# STM32F103VBT6-design.net
KiCad netlist of a schematic drawn in Altium Designer
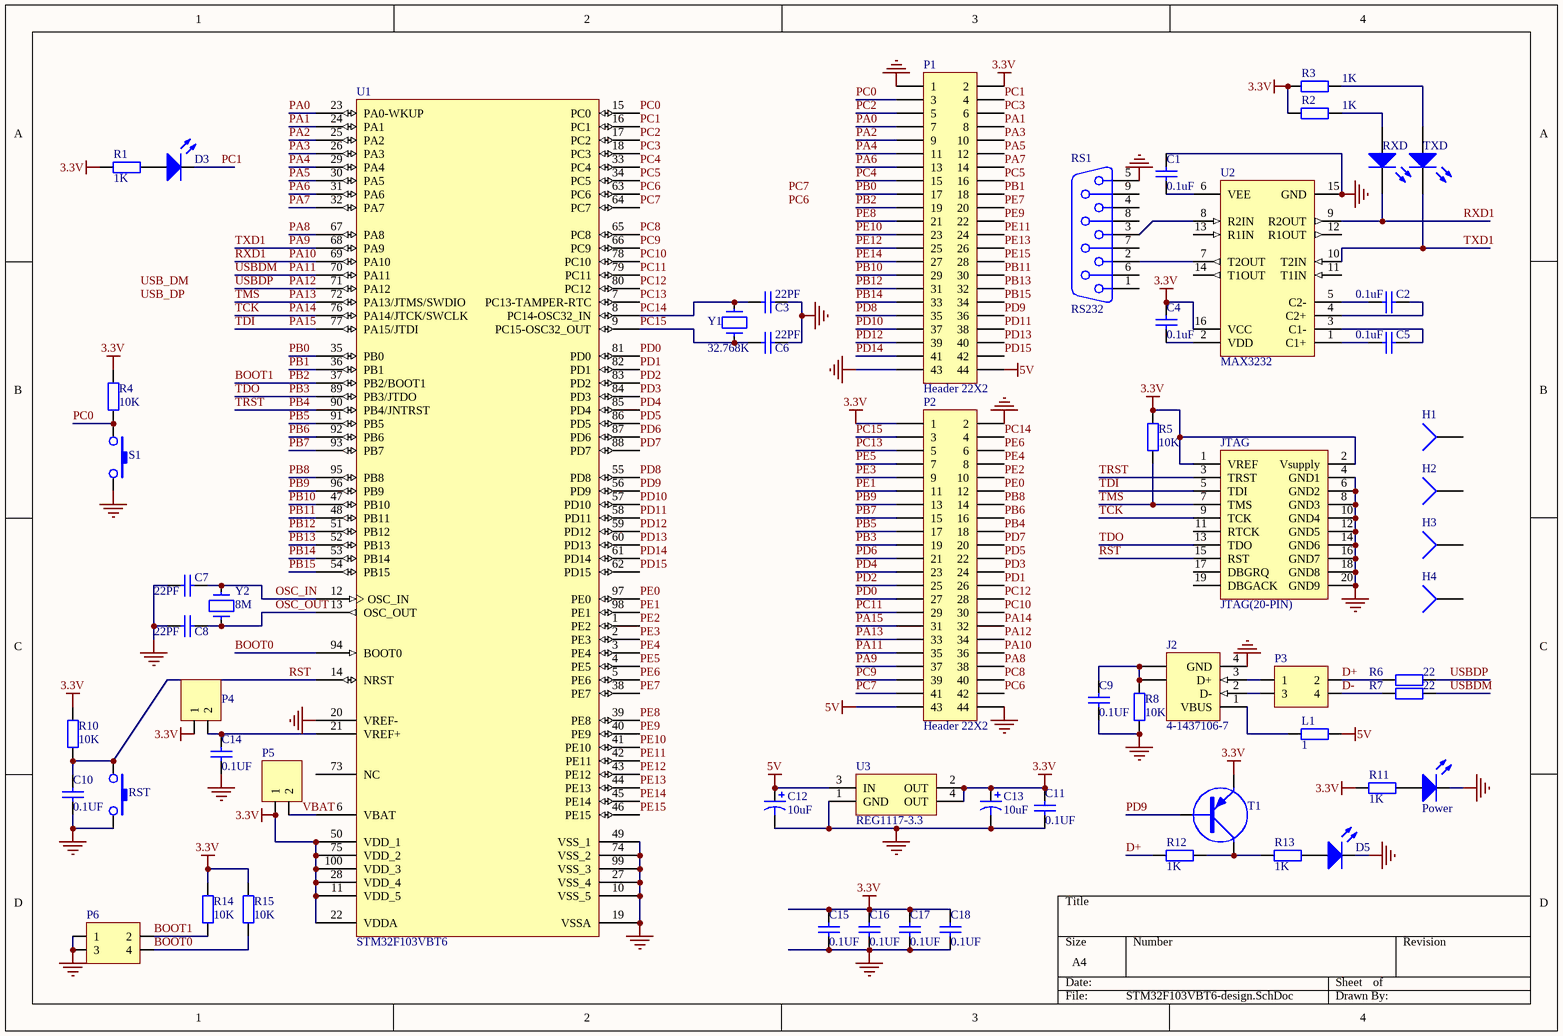
[diagram p0: STM32F103VBT6-design.SchDoc]

(export (version "E")
  (design (tool "Eeschema 10.0.6"))
  (components
    (comp (ref "C1")
      (value "0.1uF")
      (footprint "0805-S")
      (description "Capacitor")
      (fields (field (name "Comment") "Cap") (field (name "PUBLISHER") "Altium Limited"))
      (libsource (lib "Miscellaneous Devices") (part "Cap"))
    )
    (comp (ref "C2")
      (value "0.1uF")
      (footprint "0805-S")
      (description "Capacitor")
      (fields (field (name "Comment") "Cap") (field (name "PUBLISHER") "Altium Limited"))
      (libsource (lib "Miscellaneous Devices") (part "Cap"))
    )
    (comp (ref "C3")
      (value "22PF")
      (footprint "0805-S")
      (description "Capacitor")
      (fields (field (name "Comment") "Cap") (field (name "PUBLISHER") "Altium Limited"))
      (libsource (lib "Miscellaneous Devices") (part "Cap"))
    )
    (comp (ref "C4")
      (value "0.1uF")
      (footprint "0805-S")
      (description "Capacitor")
      (fields (field (name "Comment") "Cap") (field (name "PUBLISHER") "Altium Limited"))
      (libsource (lib "Miscellaneous Devices") (part "Cap"))
    )
    (comp (ref "C5")
      (value "0.1uF")
      (footprint "0805-S")
      (description "Capacitor")
      (fields (field (name "Comment") "Cap") (field (name "PUBLISHER") "Altium Limited"))
      (libsource (lib "Miscellaneous Devices") (part "Cap"))
    )
    (comp (ref "C6")
      (value "22PF")
      (footprint "0805-S")
      (description "Capacitor")
      (fields (field (name "Comment") "Cap") (field (name "PUBLISHER") "Altium Limited"))
      (libsource (lib "Miscellaneous Devices") (part "Cap"))
    )
    (comp (ref "C7")
      (value "22PF")
      (footprint "0805-S")
      (description "Capacitor")
      (fields (field (name "Comment") "Cap") (field (name "PUBLISHER") "Altium Limited"))
      (libsource (lib "Miscellaneous Devices") (part "Cap"))
    )
    (comp (ref "C8")
      (value "22PF")
      (footprint "0805-S")
      (description "Capacitor")
      (fields (field (name "Comment") "Cap") (field (name "PUBLISHER") "Altium Limited"))
      (libsource (lib "Miscellaneous Devices") (part "Cap"))
    )
    (comp (ref "C9")
      (value "0.1UF")
      (footprint "0805-S")
      (description "Capacitor")
      (fields (field (name "Comment") "Cap") (field (name "PUBLISHER") "Altium Limited"))
      (libsource (lib "Miscellaneous Devices") (part "Cap"))
    )
    (comp (ref "C10")
      (value "0.1UF")
      (footprint "0805-S")
      (description "Capacitor")
      (fields (field (name "Comment") "Cap") (field (name "PUBLISHER") "Altium Limited"))
      (libsource (lib "Miscellaneous Devices") (part "Cap"))
    )
    (comp (ref "C11")
      (value "0.1UF")
      (footprint "0805-S")
      (description "Capacitor")
      (fields (field (name "Comment") "Cap") (field (name "PUBLISHER") "Altium Limited"))
      (libsource (lib "Miscellaneous Devices") (part "Cap"))
    )
    (comp (ref "C12")
      (value "10uF")
      (footprint "C_10UF")
      (description "Polarized Capacitor (Radial)")
      (fields (field (name "Comment") "Cap Pol1") (field (name "PUBLISHER") "Altium Limited"))
      (libsource (lib "Miscellaneous Devices") (part "Cap Pol1"))
    )
    (comp (ref "C13")
      (value "10uF")
      (footprint "C_10UF")
      (description "Polarized Capacitor (Radial)")
      (fields (field (name "Comment") "Cap Pol1") (field (name "PUBLISHER") "Altium Limited"))
      (libsource (lib "Miscellaneous Devices") (part "Cap Pol1"))
    )
    (comp (ref "C14")
      (value "0.1UF")
      (footprint "0805-S")
      (description "Capacitor")
      (fields (field (name "Comment") "Cap") (field (name "PUBLISHER") "Altium Limited"))
      (libsource (lib "Miscellaneous Devices") (part "Cap"))
    )
    (comp (ref "C15")
      (value "0.1UF")
      (footprint "0805-S")
      (description "Capacitor")
      (fields (field (name "Comment") "Cap") (field (name "PUBLISHER") "Altium Limited"))
      (libsource (lib "Miscellaneous Devices") (part "Cap"))
    )
    (comp (ref "C16")
      (value "0.1UF")
      (footprint "0805-S")
      (description "Capacitor")
      (fields (field (name "Comment") "Cap") (field (name "PUBLISHER") "Altium Limited"))
      (libsource (lib "Miscellaneous Devices") (part "Cap"))
    )
    (comp (ref "C17")
      (value "0.1UF")
      (footprint "0805-S")
      (description "Capacitor")
      (fields (field (name "Comment") "Cap") (field (name "PUBLISHER") "Altium Limited"))
      (libsource (lib "Miscellaneous Devices") (part "Cap"))
    )
    (comp (ref "C18")
      (value "0.1UF")
      (footprint "0805-S")
      (description "Capacitor")
      (fields (field (name "Comment") "Cap") (field (name "PUBLISHER") "Altium Limited"))
      (libsource (lib "Miscellaneous Devices") (part "Cap"))
    )
    (comp (ref "D3")
      (value "LED1")
      (footprint "C0805")
      (description "Typical INFRARED GaAs LED")
      (fields (field (name "PUBLISHER") "Altium Limited"))
      (libsource (lib "*") (part "LED0"))
    )
    (comp (ref "D5")
      (value "LED1")
      (footprint "C0805")
      (description "Typical INFRARED GaAs LED")
      (fields (field (name "PUBLISHER") "Altium Limited"))
      (libsource (lib "*") (part "LED0"))
    )
    (comp (ref "H1")
      (value "Socket")
      (footprint "Hold_2")
      (fields (field (name "PUBLISHER") "Altium Limited"))
      (libsource (lib "Miscellaneous Connectors") (part "Socket"))
    )
    (comp (ref "H2")
      (value "Socket")
      (footprint "Hold_2")
      (fields (field (name "PUBLISHER") "Altium Limited"))
      (libsource (lib "Miscellaneous Connectors") (part "Socket"))
    )
    (comp (ref "H3")
      (value "Socket")
      (footprint "Hold_2")
      (fields (field (name "PUBLISHER") "Altium Limited"))
      (libsource (lib "Miscellaneous Connectors") (part "Socket"))
    )
    (comp (ref "H4")
      (value "Socket")
      (footprint "Hold_2")
      (fields (field (name "PUBLISHER") "Altium Limited"))
      (libsource (lib "Miscellaneous Connectors") (part "Socket"))
    )
    (comp (ref "J2")
      (value "4-1437106-7")
      (footprint "USB_B_LOGO")
      (description "USB 1.1, Right Angle, Thru-Hole, B Type, Receptacle, 4 Position, White")
      (fields (field (name "PUBLISHER") "Altium Limited"))
      (libsource (lib "AMP Serial Bus USB") (part "4-1437106-7"))
    )
    (comp (ref "JTAG") (value "JTAG(20-PIN)") (footprint "IDE20-DIP") (libsource (lib "*") (part "JTAG20")))
    (comp (ref "L1")
      (value "1")
      (footprint "0805-S")
      (description "Resistor")
      (fields (field (name "Comment") "Res2") (field (name "PUBLISHER") "Altium Limited"))
      (libsource (lib "") (part "Res2_2"))
    )
    (comp (ref "P1")
      (value "Header 22X2")
      (footprint "HDR2X22")
      (description "Header, 22-Pin, Dual row")
      (fields (field (name "PUBLISHER") "Altium Limited"))
      (libsource (lib "Miscellaneous Connectors") (part "Header 22X2"))
    )
    (comp (ref "P2")
      (value "Header 22X2")
      (footprint "HDR2X22")
      (description "Header, 22-Pin, Dual row")
      (fields (field (name "PUBLISHER") "Altium Limited"))
      (libsource (lib "Miscellaneous Connectors") (part "Header 22X2"))
    )
    (comp (ref "P3")
      (value "Header 2X2")
      (footprint "HDR2X2")
      (description "Header, 2-Pin, Dual row")
      (fields (field (name "PUBLISHER") "Altium Limited"))
      (libsource (lib "Miscellaneous Connectors") (part "Header 2X2"))
    )
    (comp (ref "P4")
      (value "Header 2")
      (footprint "HDR1X2")
      (description "Header, 2-Pin")
      (fields (field (name "PUBLISHER") "Altium Limited"))
      (libsource (lib "Miscellaneous Connectors") (part "Header 2"))
    )
    (comp (ref "P5")
      (value "Header 2")
      (footprint "HDR1X2")
      (description "Header, 2-Pin")
      (fields (field (name "PUBLISHER") "Altium Limited"))
      (libsource (lib "Miscellaneous Connectors") (part "Header 2"))
    )
    (comp (ref "P6")
      (value "Header 2X2")
      (footprint "HDR2X2")
      (description "Header, 2-Pin, Dual row")
      (fields (field (name "PUBLISHER") "Altium Limited"))
      (libsource (lib "Miscellaneous Connectors") (part "Header 2X2"))
    )
    (comp (ref "Power")
      (value "LED1")
      (footprint "C0805")
      (description "Typical INFRARED GaAs LED")
      (fields (field (name "PUBLISHER") "Altium Limited"))
      (libsource (lib "*") (part "LED0"))
    )
    (comp (ref "R1")
      (value "1K")
      (footprint "0805-S")
      (description "Resistor")
      (fields (field (name "Comment") "Res2") (field (name "PUBLISHER") "Altium Limited"))
      (libsource (lib "Miscellaneous Devices") (part "Res2"))
    )
    (comp (ref "R2")
      (value "1K")
      (footprint "0805-S")
      (description "Resistor")
      (fields (field (name "Comment") "Res2") (field (name "PUBLISHER") "Altium Limited"))
      (libsource (lib "") (part "Res2_2"))
    )
    (comp (ref "R3")
      (value "1K")
      (footprint "0805-S")
      (description "Resistor")
      (fields (field (name "Comment") "Res2") (field (name "PUBLISHER") "Altium Limited"))
      (libsource (lib "") (part "Res2_2"))
    )
    (comp (ref "R4")
      (value "10K")
      (footprint "0805-S")
      (description "Resistor")
      (fields (field (name "Comment") "Res2") (field (name "PUBLISHER") "Altium Limited"))
      (libsource (lib "") (part "Res2_1"))
    )
    (comp (ref "R5")
      (value "10K")
      (footprint "0805-S")
      (description "Resistor")
      (fields (field (name "Comment") "Res2") (field (name "PUBLISHER") "Altium Limited"))
      (libsource (lib "") (part "Res2_3"))
    )
    (comp (ref "R6")
      (value "22")
      (footprint "0805-S")
      (description "Resistor")
      (fields (field (name "Comment") "Res2") (field (name "PUBLISHER") "Altium Limited"))
      (libsource (lib "Miscellaneous Devices") (part "Res2"))
    )
    (comp (ref "R7")
      (value "22")
      (footprint "0805-S")
      (description "Resistor")
      (fields (field (name "Comment") "Res2") (field (name "PUBLISHER") "Altium Limited"))
      (libsource (lib "Miscellaneous Devices") (part "Res2"))
    )
    (comp (ref "R8")
      (value "10K")
      (footprint "0805-S")
      (description "Resistor")
      (fields (field (name "Comment") "Res2") (field (name "PUBLISHER") "Altium Limited"))
      (libsource (lib "") (part "Res2_1"))
    )
    (comp (ref "R10")
      (value "10K")
      (footprint "0805-S")
      (description "Resistor")
      (fields (field (name "Comment") "Res2") (field (name "PUBLISHER") "Altium Limited"))
      (libsource (lib "") (part "Res2_1"))
    )
    (comp (ref "R11")
      (value "1K")
      (footprint "0805-S")
      (description "Resistor")
      (fields (field (name "Comment") "Res2") (field (name "PUBLISHER") "Altium Limited"))
      (libsource (lib "Miscellaneous Devices") (part "Res2"))
    )
    (comp (ref "R12")
      (value "1K")
      (footprint "0805-S")
      (description "Resistor")
      (fields (field (name "Comment") "Res2") (field (name "PUBLISHER") "Altium Limited"))
      (libsource (lib "Miscellaneous Devices") (part "Res2"))
    )
    (comp (ref "R13")
      (value "1K")
      (footprint "0805-S")
      (description "Resistor")
      (fields (field (name "Comment") "Res2") (field (name "PUBLISHER") "Altium Limited"))
      (libsource (lib "Miscellaneous Devices") (part "Res2"))
    )
    (comp (ref "R14")
      (value "10K")
      (footprint "0805-S")
      (description "Resistor")
      (fields (field (name "Comment") "Res2") (field (name "PUBLISHER") "Altium Limited"))
      (libsource (lib "") (part "Res2_1"))
    )
    (comp (ref "R15")
      (value "10K")
      (footprint "0805-S")
      (description "Resistor")
      (fields (field (name "Comment") "Res2") (field (name "PUBLISHER") "Altium Limited"))
      (libsource (lib "") (part "Res2_1"))
    )
    (comp (ref "RS1") (value "RS232") (footprint "DSUB1.385-2H9") (libsource (lib "*") (part "DB9")))
    (comp (ref "RST") (value "SW-PB") (footprint "key-press") (libsource (lib "*") (part "SW-PB")))
    (comp (ref "RXD")
      (value "LED0")
      (footprint "C0805")
      (description "Typical INFRARED GaAs LED")
      (fields (field (name "PUBLISHER") "Altium Limited"))
      (libsource (lib "Miscellaneous Devices") (part "LED0"))
    )
    (comp (ref "S1") (value "SW-PB") (footprint "key-press") (libsource (lib "*") (part "SW-PB")))
    (comp (ref "T1")
      (value "8550")
      (footprint "BEC-123")
      (description "PNP Transistor")
      (libsource (lib "*") (part "PNP"))
    )
    (comp (ref "TXD")
      (value "LED0")
      (footprint "C0805")
      (description "Typical INFRARED GaAs LED")
      (fields (field (name "PUBLISHER") "Altium Limited"))
      (libsource (lib "Miscellaneous Devices") (part "LED0"))
    )
    (comp (ref "U1")
      (value "STM32F103VBT6")
      (footprint "LQFP100_N")
      (description "STM32 ARM-based 32-bit MCU with 64 Kbytes Flash, 100-pin LQFP, Industrial Temperature")
      (fields (field (name "PUBLISHER") "Altium Limited"))
      (libsource (lib "ST Microcontroller 32-Bit STM32") (part "STM32F103VBT6"))
    )
    (comp (ref "U2")
      (value "MAX3232")
      (footprint "SOIC16")
      (description "+5V Powered, Multi-Channel RS-232 Driver/Receiver")
      (fields (field (name "PUBLISHER") "Altium Limited"))
      (libsource (lib "Maxim Communication Transceiver") (part "MAX232ACWE"))
    )
    (comp (ref "U3")
      (value "REG1117-3.3")
      (footprint "ZZ311")
      (description "800mA and 1A Low Dropout Positive Regulator 2.85V, 3.3V, 5V, and Adjustable")
      (fields (field (name "PUBLISHER") "Altium Limited"))
      (libsource (lib "BB Power Mgt Voltage Regulator") (part "REG1117-3.3"))
    )
    (comp (ref "Y1")
      (value "32.768K")
      (footprint "32768K")
      (description "Crystal")
      (libsource (lib "*") (part "CRYSTAL"))
    )
    (comp (ref "Y2")
      (value "8M")
      (footprint "XTAL_DIP")
      (description "Crystal")
      (libsource (lib "*") (part "CRYSTAL"))
    )
  )
  (nets
    (net (code "1") (name "/BOOT0") (class "Default")
      (node (ref "P6") (pin "4") (pinfunction "4_4") (pintype "passive"))
      (node (ref "R15") (pin "1") (pinfunction "1_1") (pintype "passive"))
      (node (ref "U1") (pin "94") (pinfunction "BOOT0_94") (pintype "input"))
    )
    (net (code "2") (name "/BOOT1") (class "Default")
      (node (ref "P1") (pin "19") (pinfunction "19_19") (pintype "passive"))
      (node (ref "P6") (pin "2") (pinfunction "2_2") (pintype "passive"))
      (node (ref "R14") (pin "1") (pinfunction "1_1") (pintype "passive"))
      (node (ref "U1") (pin "37") (pinfunction "PB2/BOOT1_37") (pintype "bidirectional"))
    )
    (net (code "3") (name "/D+") (class "Default")
      (node (ref "P3") (pin "2") (pinfunction "2_2") (pintype "passive"))
      (node (ref "R12") (pin "2") (pinfunction "2_2") (pintype "passive"))
      (node (ref "R6") (pin "2") (pinfunction "2_2") (pintype "passive"))
    )
    (net (code "4") (name "/D-") (class "Default")
      (node (ref "P3") (pin "4") (pinfunction "4_4") (pintype "passive"))
      (node (ref "R7") (pin "2") (pinfunction "2_2") (pintype "passive"))
    )
    (net (code "5") (name "/OSC_IN") (class "Default")
      (node (ref "C7") (pin "1") (pinfunction "1_1") (pintype "passive"))
      (node (ref "U1") (pin "12") (pinfunction "OSC_IN_12") (pintype "input"))
      (node (ref "Y2") (pin "2") (pinfunction "2_2") (pintype "passive"))
    )
    (net (code "6") (name "/OSC_OUT") (class "Default")
      (node (ref "C8") (pin "1") (pinfunction "1_1") (pintype "passive"))
      (node (ref "U1") (pin "13") (pinfunction "OSC_OUT_13") (pintype "output"))
      (node (ref "Y2") (pin "1") (pinfunction "1_1") (pintype "passive"))
    )
    (net (code "7") (name "/PA0") (class "Default")
      (node (ref "P1") (pin "7") (pinfunction "7_7") (pintype "passive"))
      (node (ref "U1") (pin "23") (pinfunction "PA0-WKUP_23") (pintype "bidirectional"))
    )
    (net (code "8") (name "/PA1") (class "Default")
      (node (ref "P1") (pin "8") (pinfunction "8_8") (pintype "passive"))
      (node (ref "U1") (pin "24") (pinfunction "PA1_24") (pintype "bidirectional"))
    )
    (net (code "9") (name "/PA2") (class "Default")
      (node (ref "P1") (pin "9") (pinfunction "9_9") (pintype "passive"))
      (node (ref "U1") (pin "25") (pinfunction "PA2_25") (pintype "bidirectional"))
    )
    (net (code "10") (name "/PA3") (class "Default")
      (node (ref "P1") (pin "10") (pinfunction "10_10") (pintype "passive"))
      (node (ref "U1") (pin "26") (pinfunction "PA3_26") (pintype "bidirectional"))
    )
    (net (code "11") (name "/PA4") (class "Default")
      (node (ref "P1") (pin "11") (pinfunction "11_11") (pintype "passive"))
      (node (ref "U1") (pin "29") (pinfunction "PA4_29") (pintype "bidirectional"))
    )
    (net (code "12") (name "/PA5") (class "Default")
      (node (ref "P1") (pin "12") (pinfunction "12_12") (pintype "passive"))
      (node (ref "U1") (pin "30") (pinfunction "PA5_30") (pintype "bidirectional"))
    )
    (net (code "13") (name "/PA6") (class "Default")
      (node (ref "P1") (pin "13") (pinfunction "13_13") (pintype "passive"))
      (node (ref "U1") (pin "31") (pinfunction "PA6_31") (pintype "bidirectional"))
    )
    (net (code "14") (name "/PA7") (class "Default")
      (node (ref "P1") (pin "14") (pinfunction "14_14") (pintype "passive"))
      (node (ref "U1") (pin "32") (pinfunction "PA7_32") (pintype "bidirectional"))
    )
    (net (code "15") (name "/PA8") (class "Default")
      (node (ref "P2") (pin "38") (pinfunction "38_38") (pintype "passive"))
      (node (ref "U1") (pin "67") (pinfunction "PA8_67") (pintype "bidirectional"))
    )
    (net (code "16") (name "/PA9") (class "Default")
      (node (ref "P2") (pin "37") (pinfunction "37_37") (pintype "passive"))
      (node (ref "TXD") (pin "2") (pinfunction "K_2") (pintype "passive"))
      (node (ref "U1") (pin "68") (pinfunction "PA9_68") (pintype "bidirectional"))
      (node (ref "U2") (pin "10") (pinfunction "T2IN_10") (pintype "input"))
    )
    (net (code "17") (name "/PA10") (class "Default")
      (node (ref "P2") (pin "36") (pinfunction "36_36") (pintype "passive"))
      (node (ref "RXD") (pin "2") (pinfunction "K_2") (pintype "passive"))
      (node (ref "U1") (pin "69") (pinfunction "PA10_69") (pintype "bidirectional"))
      (node (ref "U2") (pin "9") (pinfunction "R2OUT_9") (pintype "output"))
    )
    (net (code "18") (name "/PA11") (class "Default")
      (node (ref "P2") (pin "35") (pinfunction "35_35") (pintype "passive"))
      (node (ref "R7") (pin "1") (pinfunction "1_1") (pintype "passive"))
      (node (ref "U1") (pin "70") (pinfunction "PA11_70") (pintype "bidirectional"))
    )
    (net (code "19") (name "/PA12") (class "Default")
      (node (ref "P2") (pin "34") (pinfunction "34_34") (pintype "passive"))
      (node (ref "R6") (pin "1") (pinfunction "1_1") (pintype "passive"))
      (node (ref "U1") (pin "71") (pinfunction "PA12_71") (pintype "bidirectional"))
    )
    (net (code "20") (name "/PA13") (class "Default")
      (node (ref "JTAG") (pin "7") (pinfunction "TMS_7") (pintype "passive"))
      (node (ref "P2") (pin "33") (pinfunction "33_33") (pintype "passive"))
      (node (ref "R5") (pin "2") (pinfunction "2_2") (pintype "passive"))
      (node (ref "U1") (pin "72") (pinfunction "PA13/JTMS/SWDIO_72") (pintype "bidirectional"))
    )
    (net (code "21") (name "/PA14") (class "Default")
      (node (ref "JTAG") (pin "9") (pinfunction "TCK_9") (pintype "passive"))
      (node (ref "P2") (pin "32") (pinfunction "32_32") (pintype "passive"))
      (node (ref "U1") (pin "76") (pinfunction "PA14/JTCK/SWCLK_76") (pintype "bidirectional"))
    )
    (net (code "22") (name "/PA15") (class "Default")
      (node (ref "JTAG") (pin "5") (pinfunction "TDI_5") (pintype "passive"))
      (node (ref "P2") (pin "31") (pinfunction "31_31") (pintype "passive"))
      (node (ref "U1") (pin "77") (pinfunction "PA15/JTDI_77") (pintype "bidirectional"))
    )
    (net (code "23") (name "/PB0") (class "Default")
      (node (ref "P1") (pin "17") (pinfunction "17_17") (pintype "passive"))
      (node (ref "U1") (pin "35") (pinfunction "PB0_35") (pintype "bidirectional"))
    )
    (net (code "24") (name "/PB1") (class "Default")
      (node (ref "P1") (pin "18") (pinfunction "18_18") (pintype "passive"))
      (node (ref "U1") (pin "36") (pinfunction "PB1_36") (pintype "bidirectional"))
    )
    (net (code "25") (name "/PB3") (class "Default")
      (node (ref "JTAG") (pin "13") (pinfunction "TDO_13") (pintype "passive"))
      (node (ref "P2") (pin "19") (pinfunction "19_19") (pintype "passive"))
      (node (ref "U1") (pin "89") (pinfunction "PB3/JTDO_89") (pintype "bidirectional"))
    )
    (net (code "26") (name "/PB4") (class "Default")
      (node (ref "JTAG") (pin "3") (pinfunction "TRST_3") (pintype "passive"))
      (node (ref "P2") (pin "18") (pinfunction "18_18") (pintype "passive"))
      (node (ref "U1") (pin "90") (pinfunction "PB4/JNTRST_90") (pintype "bidirectional"))
    )
    (net (code "27") (name "/PB5") (class "Default")
      (node (ref "P2") (pin "17") (pinfunction "17_17") (pintype "passive"))
      (node (ref "U1") (pin "91") (pinfunction "PB5_91") (pintype "bidirectional"))
    )
    (net (code "28") (name "/PB6") (class "Default")
      (node (ref "P2") (pin "16") (pinfunction "16_16") (pintype "passive"))
      (node (ref "U1") (pin "92") (pinfunction "PB6_92") (pintype "bidirectional"))
    )
    (net (code "29") (name "/PB7") (class "Default")
      (node (ref "P2") (pin "15") (pinfunction "15_15") (pintype "passive"))
      (node (ref "U1") (pin "93") (pinfunction "PB7_93") (pintype "bidirectional"))
    )
    (net (code "30") (name "/PB8") (class "Default")
      (node (ref "P2") (pin "14") (pinfunction "14_14") (pintype "passive"))
      (node (ref "U1") (pin "95") (pinfunction "PB8_95") (pintype "bidirectional"))
    )
    (net (code "31") (name "/PB9") (class "Default")
      (node (ref "P2") (pin "13") (pinfunction "13_13") (pintype "passive"))
      (node (ref "U1") (pin "96") (pinfunction "PB9_96") (pintype "bidirectional"))
    )
    (net (code "32") (name "/PB10") (class "Default")
      (node (ref "P1") (pin "29") (pinfunction "29_29") (pintype "passive"))
      (node (ref "U1") (pin "47") (pinfunction "PB10_47") (pintype "bidirectional"))
    )
    (net (code "33") (name "/PB11") (class "Default")
      (node (ref "P1") (pin "30") (pinfunction "30_30") (pintype "passive"))
      (node (ref "U1") (pin "48") (pinfunction "PB11_48") (pintype "bidirectional"))
    )
    (net (code "34") (name "/PB12") (class "Default")
      (node (ref "P1") (pin "31") (pinfunction "31_31") (pintype "passive"))
      (node (ref "U1") (pin "51") (pinfunction "PB12_51") (pintype "bidirectional"))
    )
    (net (code "35") (name "/PB13") (class "Default")
      (node (ref "P1") (pin "32") (pinfunction "32_32") (pintype "passive"))
      (node (ref "U1") (pin "52") (pinfunction "PB13_52") (pintype "bidirectional"))
    )
    (net (code "36") (name "/PB14") (class "Default")
      (node (ref "P1") (pin "33") (pinfunction "33_33") (pintype "passive"))
      (node (ref "U1") (pin "53") (pinfunction "PB14_53") (pintype "bidirectional"))
    )
    (net (code "37") (name "/PB15") (class "Default")
      (node (ref "P1") (pin "34") (pinfunction "34_34") (pintype "passive"))
      (node (ref "U1") (pin "54") (pinfunction "PB15_54") (pintype "bidirectional"))
    )
    (net (code "38") (name "/PC0") (class "Default")
      (node (ref "P1") (pin "3") (pinfunction "3_3") (pintype "passive"))
      (node (ref "R4") (pin "1") (pinfunction "1_1") (pintype "passive"))
      (node (ref "S1") (pin "1") (pinfunction "1_1") (pintype "passive"))
      (node (ref "U1") (pin "15") (pinfunction "PC0_15") (pintype "bidirectional"))
    )
    (net (code "39") (name "/PC1") (class "Default")
      (node (ref "D3") (pin "2") (pinfunction "K_2") (pintype "passive"))
      (node (ref "P1") (pin "4") (pinfunction "4_4") (pintype "passive"))
      (node (ref "U1") (pin "16") (pinfunction "PC1_16") (pintype "bidirectional"))
    )
    (net (code "40") (name "/PC2") (class "Default")
      (node (ref "P1") (pin "5") (pinfunction "5_5") (pintype "passive"))
      (node (ref "U1") (pin "17") (pinfunction "PC2_17") (pintype "bidirectional"))
    )
    (net (code "41") (name "/PC3") (class "Default")
      (node (ref "P1") (pin "6") (pinfunction "6_6") (pintype "passive"))
      (node (ref "U1") (pin "18") (pinfunction "PC3_18") (pintype "bidirectional"))
    )
    (net (code "42") (name "/PC4") (class "Default")
      (node (ref "P1") (pin "15") (pinfunction "15_15") (pintype "passive"))
      (node (ref "U1") (pin "33") (pinfunction "PC4_33") (pintype "bidirectional"))
    )
    (net (code "43") (name "/PC5") (class "Default")
      (node (ref "P1") (pin "16") (pinfunction "16_16") (pintype "passive"))
      (node (ref "U1") (pin "34") (pinfunction "PC5_34") (pintype "bidirectional"))
    )
    (net (code "44") (name "/PC6") (class "Default")
      (node (ref "P2") (pin "42") (pinfunction "42_42") (pintype "passive"))
      (node (ref "U1") (pin "63") (pinfunction "PC6_63") (pintype "bidirectional"))
    )
    (net (code "45") (name "/PC7") (class "Default")
      (node (ref "P2") (pin "41") (pinfunction "41_41") (pintype "passive"))
      (node (ref "U1") (pin "64") (pinfunction "PC7_64") (pintype "bidirectional"))
    )
    (net (code "46") (name "/PC8") (class "Default")
      (node (ref "P2") (pin "40") (pinfunction "40_40") (pintype "passive"))
      (node (ref "U1") (pin "65") (pinfunction "PC8_65") (pintype "bidirectional"))
    )
    (net (code "47") (name "/PC9") (class "Default")
      (node (ref "P2") (pin "39") (pinfunction "39_39") (pintype "passive"))
      (node (ref "U1") (pin "66") (pinfunction "PC9_66") (pintype "bidirectional"))
    )
    (net (code "48") (name "/PC10") (class "Default")
      (node (ref "P2") (pin "30") (pinfunction "30_30") (pintype "passive"))
      (node (ref "U1") (pin "78") (pinfunction "PC10_78") (pintype "bidirectional"))
    )
    (net (code "49") (name "/PC11") (class "Default")
      (node (ref "P2") (pin "29") (pinfunction "29_29") (pintype "passive"))
      (node (ref "U1") (pin "79") (pinfunction "PC11_79") (pintype "bidirectional"))
    )
    (net (code "50") (name "/PC12") (class "Default")
      (node (ref "P2") (pin "28") (pinfunction "28_28") (pintype "passive"))
      (node (ref "U1") (pin "80") (pinfunction "PC12_80") (pintype "bidirectional"))
    )
    (net (code "51") (name "/PC13") (class "Default")
      (node (ref "P2") (pin "5") (pinfunction "5_5") (pintype "passive"))
      (node (ref "U1") (pin "7") (pinfunction "PC13-TAMPER-RTC_7") (pintype "bidirectional"))
    )
    (net (code "52") (name "/PC14") (class "Default")
      (node (ref "C3") (pin "1") (pinfunction "1_1") (pintype "passive"))
      (node (ref "P2") (pin "4") (pinfunction "4_4") (pintype "passive"))
      (node (ref "U1") (pin "8") (pinfunction "PC14-OSC32_IN_8") (pintype "bidirectional"))
      (node (ref "Y1") (pin "1") (pinfunction "1_1") (pintype "passive"))
    )
    (net (code "53") (name "/PC15") (class "Default")
      (node (ref "C6") (pin "1") (pinfunction "1_1") (pintype "passive"))
      (node (ref "P2") (pin "3") (pinfunction "3_3") (pintype "passive"))
      (node (ref "U1") (pin "9") (pinfunction "PC15-OSC32_OUT_9") (pintype "bidirectional"))
      (node (ref "Y1") (pin "2") (pinfunction "2_2") (pintype "passive"))
    )
    (net (code "54") (name "/PD0") (class "Default")
      (node (ref "P2") (pin "27") (pinfunction "27_27") (pintype "passive"))
      (node (ref "U1") (pin "81") (pinfunction "PD0_81") (pintype "bidirectional"))
    )
    (net (code "55") (name "/PD1") (class "Default")
      (node (ref "P2") (pin "26") (pinfunction "26_26") (pintype "passive"))
      (node (ref "U1") (pin "82") (pinfunction "PD1_82") (pintype "bidirectional"))
    )
    (net (code "56") (name "/PD2") (class "Default")
      (node (ref "P2") (pin "25") (pinfunction "25_25") (pintype "passive"))
      (node (ref "U1") (pin "83") (pinfunction "PD2_83") (pintype "bidirectional"))
    )
    (net (code "57") (name "/PD3") (class "Default")
      (node (ref "P2") (pin "24") (pinfunction "24_24") (pintype "passive"))
      (node (ref "U1") (pin "84") (pinfunction "PD3_84") (pintype "bidirectional"))
    )
    (net (code "58") (name "/PD4") (class "Default")
      (node (ref "P2") (pin "23") (pinfunction "23_23") (pintype "passive"))
      (node (ref "U1") (pin "85") (pinfunction "PD4_85") (pintype "bidirectional"))
    )
    (net (code "59") (name "/PD5") (class "Default")
      (node (ref "P2") (pin "22") (pinfunction "22_22") (pintype "passive"))
      (node (ref "U1") (pin "86") (pinfunction "PD5_86") (pintype "bidirectional"))
    )
    (net (code "60") (name "/PD6") (class "Default")
      (node (ref "P2") (pin "21") (pinfunction "21_21") (pintype "passive"))
      (node (ref "U1") (pin "87") (pinfunction "PD6_87") (pintype "bidirectional"))
    )
    (net (code "61") (name "/PD7") (class "Default")
      (node (ref "P2") (pin "20") (pinfunction "20_20") (pintype "passive"))
      (node (ref "U1") (pin "88") (pinfunction "PD7_88") (pintype "bidirectional"))
    )
    (net (code "62") (name "/PD8") (class "Default")
      (node (ref "P1") (pin "35") (pinfunction "35_35") (pintype "passive"))
      (node (ref "U1") (pin "55") (pinfunction "PD8_55") (pintype "bidirectional"))
    )
    (net (code "63") (name "/PD9") (class "Default")
      (node (ref "P1") (pin "36") (pinfunction "36_36") (pintype "passive"))
      (node (ref "T1") (pin "1") (pinfunction "B_1") (pintype "passive"))
      (node (ref "U1") (pin "56") (pinfunction "PD9_56") (pintype "bidirectional"))
    )
    (net (code "64") (name "/PD10") (class "Default")
      (node (ref "P1") (pin "37") (pinfunction "37_37") (pintype "passive"))
      (node (ref "U1") (pin "57") (pinfunction "PD10_57") (pintype "bidirectional"))
    )
    (net (code "65") (name "/PD11") (class "Default")
      (node (ref "P1") (pin "38") (pinfunction "38_38") (pintype "passive"))
      (node (ref "U1") (pin "58") (pinfunction "PD11_58") (pintype "bidirectional"))
    )
    (net (code "66") (name "/PD12") (class "Default")
      (node (ref "P1") (pin "39") (pinfunction "39_39") (pintype "passive"))
      (node (ref "U1") (pin "59") (pinfunction "PD12_59") (pintype "bidirectional"))
    )
    (net (code "67") (name "/PD13") (class "Default")
      (node (ref "P1") (pin "40") (pinfunction "40_40") (pintype "passive"))
      (node (ref "U1") (pin "60") (pinfunction "PD13_60") (pintype "bidirectional"))
    )
    (net (code "68") (name "/PD14") (class "Default")
      (node (ref "P1") (pin "41") (pinfunction "41_41") (pintype "passive"))
      (node (ref "U1") (pin "61") (pinfunction "PD14_61") (pintype "bidirectional"))
    )
    (net (code "69") (name "/PD15") (class "Default")
      (node (ref "P1") (pin "42") (pinfunction "42_42") (pintype "passive"))
      (node (ref "U1") (pin "62") (pinfunction "PD15_62") (pintype "bidirectional"))
    )
    (net (code "70") (name "/PE0") (class "Default")
      (node (ref "P2") (pin "12") (pinfunction "12_12") (pintype "passive"))
      (node (ref "U1") (pin "97") (pinfunction "PE0_97") (pintype "bidirectional"))
    )
    (net (code "71") (name "/PE1") (class "Default")
      (node (ref "P2") (pin "11") (pinfunction "11_11") (pintype "passive"))
      (node (ref "U1") (pin "98") (pinfunction "PE1_98") (pintype "bidirectional"))
    )
    (net (code "72") (name "/PE2") (class "Default")
      (node (ref "P2") (pin "10") (pinfunction "10_10") (pintype "passive"))
      (node (ref "U1") (pin "1") (pinfunction "PE2_1") (pintype "bidirectional"))
    )
    (net (code "73") (name "/PE3") (class "Default")
      (node (ref "P2") (pin "9") (pinfunction "9_9") (pintype "passive"))
      (node (ref "U1") (pin "2") (pinfunction "PE3_2") (pintype "bidirectional"))
    )
    (net (code "74") (name "/PE4") (class "Default")
      (node (ref "P2") (pin "8") (pinfunction "8_8") (pintype "passive"))
      (node (ref "U1") (pin "3") (pinfunction "PE4_3") (pintype "bidirectional"))
    )
    (net (code "75") (name "/PE5") (class "Default")
      (node (ref "P2") (pin "7") (pinfunction "7_7") (pintype "passive"))
      (node (ref "U1") (pin "4") (pinfunction "PE5_4") (pintype "bidirectional"))
    )
    (net (code "76") (name "/PE6") (class "Default")
      (node (ref "P2") (pin "6") (pinfunction "6_6") (pintype "passive"))
      (node (ref "U1") (pin "5") (pinfunction "PE6_5") (pintype "bidirectional"))
    )
    (net (code "77") (name "/PE7") (class "Default")
      (node (ref "P1") (pin "20") (pinfunction "20_20") (pintype "passive"))
      (node (ref "U1") (pin "38") (pinfunction "PE7_38") (pintype "bidirectional"))
    )
    (net (code "78") (name "/PE8") (class "Default")
      (node (ref "P1") (pin "21") (pinfunction "21_21") (pintype "passive"))
      (node (ref "U1") (pin "39") (pinfunction "PE8_39") (pintype "bidirectional"))
    )
    (net (code "79") (name "/PE9") (class "Default")
      (node (ref "P1") (pin "22") (pinfunction "22_22") (pintype "passive"))
      (node (ref "U1") (pin "40") (pinfunction "PE9_40") (pintype "bidirectional"))
    )
    (net (code "80") (name "/PE10") (class "Default")
      (node (ref "P1") (pin "23") (pinfunction "23_23") (pintype "passive"))
      (node (ref "U1") (pin "41") (pinfunction "PE10_41") (pintype "bidirectional"))
    )
    (net (code "81") (name "/PE11") (class "Default")
      (node (ref "P1") (pin "24") (pinfunction "24_24") (pintype "passive"))
      (node (ref "U1") (pin "42") (pinfunction "PE11_42") (pintype "bidirectional"))
    )
    (net (code "82") (name "/PE12") (class "Default")
      (node (ref "P1") (pin "25") (pinfunction "25_25") (pintype "passive"))
      (node (ref "U1") (pin "43") (pinfunction "PE12_43") (pintype "bidirectional"))
    )
    (net (code "83") (name "/PE13") (class "Default")
      (node (ref "P1") (pin "26") (pinfunction "26_26") (pintype "passive"))
      (node (ref "U1") (pin "44") (pinfunction "PE13_44") (pintype "bidirectional"))
    )
    (net (code "84") (name "/PE14") (class "Default")
      (node (ref "P1") (pin "27") (pinfunction "27_27") (pintype "passive"))
      (node (ref "U1") (pin "45") (pinfunction "PE14_45") (pintype "bidirectional"))
    )
    (net (code "85") (name "/PE15") (class "Default")
      (node (ref "P1") (pin "28") (pinfunction "28_28") (pintype "passive"))
      (node (ref "U1") (pin "46") (pinfunction "PE15_46") (pintype "bidirectional"))
    )
    (net (code "86") (name "/RST") (class "Default")
      (node (ref "C10") (pin "1") (pinfunction "1_1") (pintype "passive"))
      (node (ref "JTAG") (pin "15") (pinfunction "RST_15") (pintype "passive"))
      (node (ref "R10") (pin "1") (pinfunction "1_1") (pintype "passive"))
      (node (ref "RST") (pin "1") (pinfunction "1_1") (pintype "passive"))
      (node (ref "U1") (pin "14") (pinfunction "NRST_14") (pintype "bidirectional"))
    )
    (net (code "89") (name "/VBAT") (class "Default")
      (node (ref "P5") (pin "2") (pinfunction "2_2") (pintype "passive"))
      (node (ref "U1") (pin "6") (pinfunction "VBAT_6") (pintype "power_in"))
    )
    (net (code "90") (name "3.3V") (class "Default")
      (node (ref "C11") (pin "1") (pinfunction "1_1") (pintype "passive"))
      (node (ref "C13") (pin "1") (pinfunction "1_1") (pintype "passive"))
      (node (ref "C15") (pin "1") (pinfunction "1_1") (pintype "passive"))
      (node (ref "C16") (pin "1") (pinfunction "1_1") (pintype "passive"))
      (node (ref "C17") (pin "1") (pinfunction "1_1") (pintype "passive"))
      (node (ref "C18") (pin "1") (pinfunction "1_1") (pintype "passive"))
      (node (ref "C4") (pin "2") (pinfunction "2_2") (pintype "passive"))
      (node (ref "JTAG") (pin "1") (pinfunction "VREF_1") (pintype "passive"))
      (node (ref "JTAG") (pin "2") (pinfunction "Vsupply_2") (pintype "passive"))
      (node (ref "P1") (pin "2") (pinfunction "2_2") (pintype "passive"))
      (node (ref "P2") (pin "1") (pinfunction "1_1") (pintype "passive"))
      (node (ref "P4") (pin "1") (pinfunction "1_1") (pintype "passive"))
      (node (ref "P5") (pin "1") (pinfunction "1_1") (pintype "passive"))
      (node (ref "R1") (pin "2") (pinfunction "2_2") (pintype "passive"))
      (node (ref "R10") (pin "2") (pinfunction "2_2") (pintype "passive"))
      (node (ref "R11") (pin "2") (pinfunction "2_2") (pintype "passive"))
      (node (ref "R14") (pin "2") (pinfunction "2_2") (pintype "passive"))
      (node (ref "R15") (pin "2") (pinfunction "2_2") (pintype "passive"))
      (node (ref "R2") (pin "1") (pinfunction "1_1") (pintype "passive"))
      (node (ref "R3") (pin "1") (pinfunction "1_1") (pintype "passive"))
      (node (ref "R4") (pin "2") (pinfunction "2_2") (pintype "passive"))
      (node (ref "R5") (pin "1") (pinfunction "1_1") (pintype "passive"))
      (node (ref "T1") (pin "2") (pinfunction "E_2") (pintype "passive"))
      (node (ref "U1") (pin "100") (pinfunction "VDD_3_100") (pintype "power_in"))
      (node (ref "U1") (pin "11") (pinfunction "VDD_5_11") (pintype "power_in"))
      (node (ref "U1") (pin "22") (pinfunction "VDDA_22") (pintype "power_in"))
      (node (ref "U1") (pin "28") (pinfunction "VDD_4_28") (pintype "power_in"))
      (node (ref "U1") (pin "50") (pinfunction "VDD_1_50") (pintype "power_in"))
      (node (ref "U1") (pin "75") (pinfunction "VDD_2_75") (pintype "power_in"))
      (node (ref "U2") (pin "16") (pinfunction "VCC_16") (pintype "power_in"))
      (node (ref "U3") (pin "2") (pinfunction "OUT_2") (pintype "power_in"))
      (node (ref "U3") (pin "4") (pinfunction "OUT_4") (pintype "power_in"))
    )
    (net (code "91") (name "5V") (class "Default")
      (node (ref "C12") (pin "1") (pinfunction "1_1") (pintype "passive"))
      (node (ref "L1") (pin "2") (pinfunction "2_2") (pintype "passive"))
      (node (ref "P1") (pin "44") (pinfunction "44_44") (pintype "passive"))
      (node (ref "P2") (pin "43") (pinfunction "43_43") (pintype "passive"))
      (node (ref "U3") (pin "3") (pinfunction "IN_3") (pintype "power_in"))
    )
    (net (code "92") (name "GND") (class "Default")
      (node (ref "C1") (pin "2") (pinfunction "2_2") (pintype "passive"))
      (node (ref "C10") (pin "2") (pinfunction "2_2") (pintype "passive"))
      (node (ref "C11") (pin "2") (pinfunction "2_2") (pintype "passive"))
      (node (ref "C12") (pin "2") (pinfunction "2_2") (pintype "passive"))
      (node (ref "C13") (pin "2") (pinfunction "2_2") (pintype "passive"))
      (node (ref "C14") (pin "2") (pinfunction "2_2") (pintype "passive"))
      (node (ref "C15") (pin "2") (pinfunction "2_2") (pintype "passive"))
      (node (ref "C16") (pin "2") (pinfunction "2_2") (pintype "passive"))
      (node (ref "C17") (pin "2") (pinfunction "2_2") (pintype "passive"))
      (node (ref "C18") (pin "2") (pinfunction "2_2") (pintype "passive"))
      (node (ref "C3") (pin "2") (pinfunction "2_2") (pintype "passive"))
      (node (ref "C6") (pin "2") (pinfunction "2_2") (pintype "passive"))
      (node (ref "C7") (pin "2") (pinfunction "2_2") (pintype "passive"))
      (node (ref "C8") (pin "2") (pinfunction "2_2") (pintype "passive"))
      (node (ref "C9") (pin "2") (pinfunction "2_2") (pintype "passive"))
      (node (ref "D5") (pin "2") (pinfunction "K_2") (pintype "passive"))
      (node (ref "J2") (pin "4") (pinfunction "GND_4") (pintype "power_in"))
      (node (ref "JTAG") (pin "10") (pinfunction "GND4_10") (pintype "passive"))
      (node (ref "JTAG") (pin "12") (pinfunction "GND5_12") (pintype "passive"))
      (node (ref "JTAG") (pin "14") (pinfunction "GND6_14") (pintype "passive"))
      (node (ref "JTAG") (pin "16") (pinfunction "GND7_16") (pintype "passive"))
      (node (ref "JTAG") (pin "18") (pinfunction "GND8_18") (pintype "passive"))
      (node (ref "JTAG") (pin "20") (pinfunction "GND9_20") (pintype "passive"))
      (node (ref "JTAG") (pin "4") (pinfunction "GND1_4") (pintype "passive"))
      (node (ref "JTAG") (pin "6") (pinfunction "GND2_6") (pintype "passive"))
      (node (ref "JTAG") (pin "8") (pinfunction "GND3_8") (pintype "passive"))
      (node (ref "P1") (pin "1") (pinfunction "1_1") (pintype "passive"))
      (node (ref "P1") (pin "43") (pinfunction "43_43") (pintype "passive"))
      (node (ref "P2") (pin "2") (pinfunction "2_2") (pintype "passive"))
      (node (ref "P2") (pin "44") (pinfunction "44_44") (pintype "passive"))
      (node (ref "P6") (pin "1") (pinfunction "1_1") (pintype "passive"))
      (node (ref "P6") (pin "3") (pinfunction "3_3") (pintype "passive"))
      (node (ref "Power") (pin "2") (pinfunction "K_2") (pintype "passive"))
      (node (ref "R8") (pin "1") (pinfunction "1_1") (pintype "passive"))
      (node (ref "RS1") (pin "5") (pinfunction "5_5") (pintype "passive"))
      (node (ref "RST") (pin "2") (pinfunction "2_2") (pintype "passive"))
      (node (ref "S1") (pin "2") (pinfunction "2_2") (pintype "passive"))
      (node (ref "U1") (pin "10") (pinfunction "VSS_5_10") (pintype "power_in"))
      (node (ref "U1") (pin "19") (pinfunction "VSSA_19") (pintype "power_in"))
      (node (ref "U1") (pin "20") (pinfunction "VREF-_20") (pintype "power_in"))
      (node (ref "U1") (pin "27") (pinfunction "VSS_4_27") (pintype "power_in"))
      (node (ref "U1") (pin "49") (pinfunction "VSS_1_49") (pintype "power_in"))
      (node (ref "U1") (pin "74") (pinfunction "VSS_2_74") (pintype "power_in"))
      (node (ref "U1") (pin "99") (pinfunction "VSS_3_99") (pintype "power_in"))
      (node (ref "U2") (pin "15") (pinfunction "GND_15") (pintype "power_in"))
      (node (ref "U3") (pin "1") (pinfunction "GND_1") (pintype "power_in"))
    )
    (net (code "93") (name "Net-(C9-Pad1)") (class "Default")
      (node (ref "C9") (pin "1") (pinfunction "1_1") (pintype "passive"))
      (node (ref "J2") (pin "5") (pinfunction "SHLD_5") (pintype "passive"))
      (node (ref "J2") (pin "6") (pinfunction "SHLD_6") (pintype "passive"))
      (node (ref "R8") (pin "2") (pinfunction "2_2") (pintype "passive"))
    )
    (net (code "94") (name "Net-(D3-A)") (class "Default")
      (node (ref "D3") (pin "1") (pinfunction "A_1") (pintype "passive"))
      (node (ref "R1") (pin "1") (pinfunction "1_1") (pintype "passive"))
    )
    (net (code "95") (name "Net-(D5-A)") (class "Default")
      (node (ref "D5") (pin "1") (pinfunction "A_1") (pintype "passive"))
      (node (ref "R13") (pin "1") (pinfunction "1_1") (pintype "passive"))
    )
    (net (code "96") (name "Net-(J2-D+)") (class "Default")
      (node (ref "J2") (pin "3") (pinfunction "D+_3") (pintype "input"))
      (node (ref "P3") (pin "1") (pinfunction "1_1") (pintype "passive"))
    )
    (net (code "97") (name "Net-(J2-D-)") (class "Default")
      (node (ref "J2") (pin "2") (pinfunction "D-_2") (pintype "input"))
      (node (ref "P3") (pin "3") (pinfunction "3_3") (pintype "passive"))
    )
    (net (code "98") (name "Net-(J2-VBUS)") (class "Default")
      (node (ref "J2") (pin "1") (pinfunction "VBUS_1") (pintype "power_in"))
      (node (ref "L1") (pin "1") (pinfunction "1_1") (pintype "passive"))
    )
    (net (code "99") (name "Net-(Power-A)") (class "Default")
      (node (ref "Power") (pin "1") (pinfunction "A_1") (pintype "passive"))
      (node (ref "R11") (pin "1") (pinfunction "1_1") (pintype "passive"))
    )
    (net (code "100") (name "Net-(RXD-A)") (class "Default")
      (node (ref "R2") (pin "2") (pinfunction "2_2") (pintype "passive"))
      (node (ref "RXD") (pin "1") (pinfunction "A_1") (pintype "passive"))
    )
    (net (code "101") (name "Net-(T1-C)") (class "Default")
      (node (ref "R12") (pin "1") (pinfunction "1_1") (pintype "passive"))
      (node (ref "R13") (pin "2") (pinfunction "2_2") (pintype "passive"))
      (node (ref "T1") (pin "3") (pinfunction "C_3") (pintype "passive"))
    )
    (net (code "102") (name "Net-(TXD-A)") (class "Default")
      (node (ref "R3") (pin "2") (pinfunction "2_2") (pintype "passive"))
      (node (ref "TXD") (pin "1") (pinfunction "A_1") (pintype "passive"))
    )
    (net (code "103") (name "Net-(U1-VREF+)") (class "Default")
      (node (ref "C14") (pin "1") (pinfunction "1_1") (pintype "passive"))
      (node (ref "P4") (pin "2") (pinfunction "2_2") (pintype "passive"))
      (node (ref "U1") (pin "21") (pinfunction "VREF+_21") (pintype "power_in"))
    )
    (net (code "104") (name "Net-(U2-C1+)") (class "Default")
      (node (ref "C5") (pin "1") (pinfunction "1_1") (pintype "passive"))
      (node (ref "U2") (pin "1") (pinfunction "C1+_1") (pintype "passive"))
    )
    (net (code "105") (name "Net-(U2-C1-)") (class "Default")
      (node (ref "C5") (pin "2") (pinfunction "2_2") (pintype "passive"))
      (node (ref "U2") (pin "3") (pinfunction "C1-_3") (pintype "passive"))
    )
    (net (code "106") (name "Net-(U2-C2+)") (class "Default")
      (node (ref "C2") (pin "2") (pinfunction "2_2") (pintype "passive"))
      (node (ref "U2") (pin "4") (pinfunction "C2+_4") (pintype "passive"))
    )
    (net (code "107") (name "Net-(U2-C2-)") (class "Default")
      (node (ref "C2") (pin "1") (pinfunction "1_1") (pintype "passive"))
      (node (ref "U2") (pin "5") (pinfunction "C2-_5") (pintype "passive"))
    )
    (net (code "108") (name "Net-(U2-R2IN)") (class "Default")
      (node (ref "RS1") (pin "3") (pinfunction "3_3") (pintype "passive"))
      (node (ref "U2") (pin "8") (pinfunction "R2IN_8") (pintype "input"))
    )
    (net (code "109") (name "Net-(U2-T2OUT)") (class "Default")
      (node (ref "RS1") (pin "2") (pinfunction "2_2") (pintype "passive"))
      (node (ref "U2") (pin "7") (pinfunction "T2OUT_7") (pintype "output"))
    )
    (net (code "110") (name "Net-(U2-VDD)") (class "Default")
      (node (ref "C4") (pin "1") (pinfunction "1_1") (pintype "passive"))
      (node (ref "U2") (pin "2") (pinfunction "VDD_2") (pintype "power_in"))
    )
    (net (code "111") (name "Net-(U2-VEE)") (class "Default")
      (node (ref "C1") (pin "1") (pinfunction "1_1") (pintype "passive"))
      (node (ref "U2") (pin "6") (pinfunction "VEE_6") (pintype "power_in"))
    )
    (net (code "112") (name "unconnected-(H1-Pad1)") (class "Default")
      (node (ref "H1") (pin "1") (pinfunction "1_1") (pintype "passive"))
    )
    (net (code "113") (name "unconnected-(H2-Pad1)") (class "Default")
      (node (ref "H2") (pin "1") (pinfunction "1_1") (pintype "passive"))
    )
    (net (code "114") (name "unconnected-(H3-Pad1)") (class "Default")
      (node (ref "H3") (pin "1") (pinfunction "1_1") (pintype "passive"))
    )
    (net (code "115") (name "unconnected-(H4-Pad1)") (class "Default")
      (node (ref "H4") (pin "1") (pinfunction "1_1") (pintype "passive"))
    )
    (net (code "116") (name "unconnected-(JTAG-DBGACK-Pad19)") (class "Default")
      (node (ref "JTAG") (pin "19") (pinfunction "DBGACK_19") (pintype "passive"))
    )
    (net (code "117") (name "unconnected-(JTAG-DBGRQ-Pad17)") (class "Default")
      (node (ref "JTAG") (pin "17") (pinfunction "DBGRQ_17") (pintype "passive"))
    )
    (net (code "118") (name "unconnected-(JTAG-RTCK-Pad11)") (class "Default")
      (node (ref "JTAG") (pin "11") (pinfunction "RTCK_11") (pintype "passive"))
    )
    (net (code "119") (name "unconnected-(RS1-Pad1)") (class "Default")
      (node (ref "RS1") (pin "1") (pinfunction "1_1") (pintype "passive"))
    )
    (net (code "120") (name "unconnected-(RS1-Pad4)") (class "Default")
      (node (ref "RS1") (pin "4") (pinfunction "4_4") (pintype "passive"))
    )
    (net (code "121") (name "unconnected-(RS1-Pad6)") (class "Default")
      (node (ref "RS1") (pin "6") (pinfunction "6_6") (pintype "passive"))
    )
    (net (code "122") (name "unconnected-(RS1-Pad7)") (class "Default")
      (node (ref "RS1") (pin "7") (pinfunction "7_7") (pintype "passive"))
    )
    (net (code "123") (name "unconnected-(RS1-Pad8)") (class "Default")
      (node (ref "RS1") (pin "8") (pinfunction "8_8") (pintype "passive"))
    )
    (net (code "124") (name "unconnected-(RS1-Pad9)") (class "Default")
      (node (ref "RS1") (pin "9") (pinfunction "9_9") (pintype "passive"))
    )
    (net (code "125") (name "unconnected-(U1-NC-Pad73)") (class "Default")
      (node (ref "U1") (pin "73") (pinfunction "NC_73") (pintype "passive"))
    )
    (net (code "126") (name "unconnected-(U2-R1IN-Pad13)") (class "Default")
      (node (ref "U2") (pin "13") (pinfunction "R1IN_13") (pintype "input"))
    )
    (net (code "127") (name "unconnected-(U2-R1OUT-Pad12)") (class "Default")
      (node (ref "U2") (pin "12") (pinfunction "R1OUT_12") (pintype "output"))
    )
    (net (code "128") (name "unconnected-(U2-T1IN-Pad11)") (class "Default")
      (node (ref "U2") (pin "11") (pinfunction "T1IN_11") (pintype "input"))
    )
    (net (code "129") (name "unconnected-(U2-T1OUT-Pad14)") (class "Default")
      (node (ref "U2") (pin "14") (pinfunction "T1OUT_14") (pintype "output"))
    )
  )
)
